# FTDIJtagConversion.net
KiCad netlist of a schematic drawn in Altium Designer
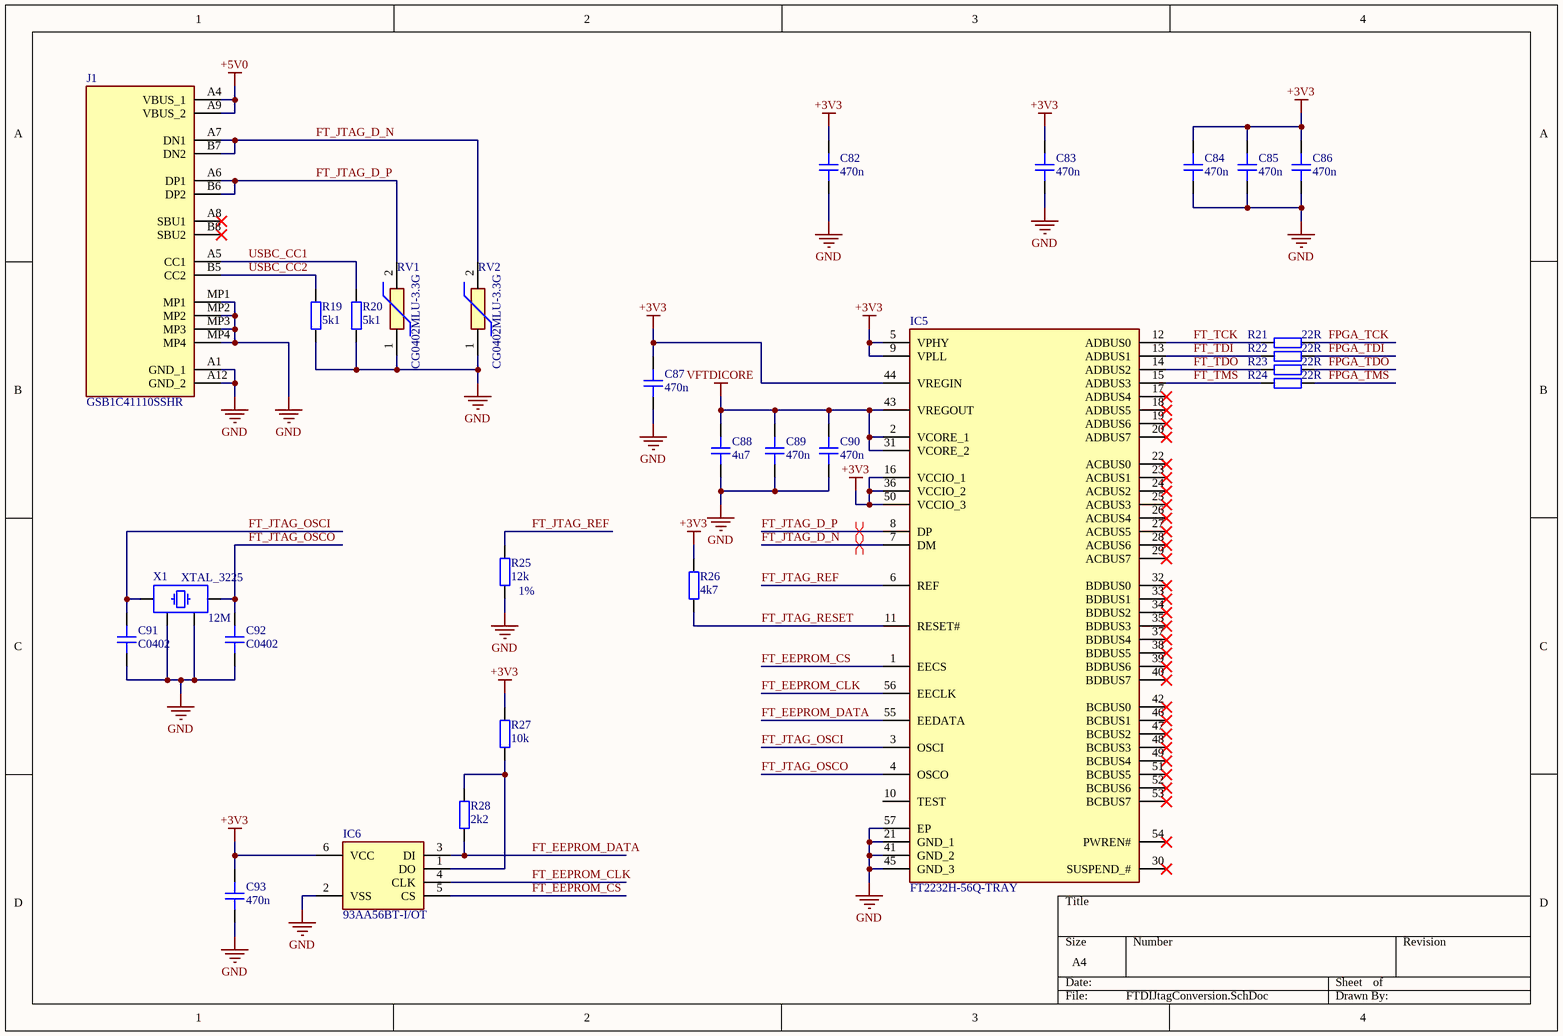
[diagram p0: FTDIJtagConversion.SchDoc]

(export (version "E")
  (design (tool "Eeschema 10.0.6"))
  (components
    (comp (ref "C82")
      (value "470n")
      (footprint "CAP_0201")
      (description "Capacitor SMD 0201")
      (libsource (lib "Schematic-Lib-PhilsLab") (part "CAP_0201"))
    )
    (comp (ref "C83")
      (value "470n")
      (footprint "CAP_0201")
      (description "Capacitor SMD 0201")
      (libsource (lib "Schematic-Lib-PhilsLab") (part "CAP_0201"))
    )
    (comp (ref "C84")
      (value "470n")
      (footprint "CAP_0201")
      (description "Capacitor SMD 0201")
      (libsource (lib "Schematic-Lib-PhilsLab") (part "CAP_0201"))
    )
    (comp (ref "C85")
      (value "470n")
      (footprint "CAP_0201")
      (description "Capacitor SMD 0201")
      (libsource (lib "Schematic-Lib-PhilsLab") (part "CAP_0201"))
    )
    (comp (ref "C86")
      (value "470n")
      (footprint "CAP_0201")
      (description "Capacitor SMD 0201")
      (libsource (lib "Schematic-Lib-PhilsLab") (part "CAP_0201"))
    )
    (comp (ref "C87")
      (value "470n")
      (footprint "CAP_0201")
      (description "Capacitor SMD 0201")
      (libsource (lib "Schematic-Lib-PhilsLab") (part "CAP_0201"))
    )
    (comp (ref "C88")
      (value "4u7")
      (footprint "CAP_0402")
      (description "Capacitor SMD 0402")
      (libsource (lib "Schematic-Lib-PhilsLab") (part "CAP_0402"))
    )
    (comp (ref "C89")
      (value "470n")
      (footprint "CAP_0201")
      (description "Capacitor SMD 0201")
      (libsource (lib "Schematic-Lib-PhilsLab") (part "CAP_0201"))
    )
    (comp (ref "C90")
      (value "470n")
      (footprint "CAP_0201")
      (description "Capacitor SMD 0201")
      (libsource (lib "Schematic-Lib-PhilsLab") (part "CAP_0201"))
    )
    (comp (ref "C91")
      (value "C0402")
      (footprint "CAP_0402")
      (description "Capacitor SMD 0402")
      (libsource (lib "Schematic-Lib-PhilsLab") (part "CAP_0402"))
    )
    (comp (ref "C92")
      (value "C0402")
      (footprint "CAP_0402")
      (description "Capacitor SMD 0402")
      (libsource (lib "Schematic-Lib-PhilsLab") (part "CAP_0402"))
    )
    (comp (ref "C93")
      (value "470n")
      (footprint "CAP_0201")
      (description "Capacitor SMD 0201")
      (libsource (lib "Schematic-Lib-PhilsLab") (part "CAP_0201"))
    )
    (comp (ref "IC5")
      (value "FT2232H-56Q-TRAY")
      (footprint "Footprint-Lib-PhilsLab:QFN50P800X800X100-57N-D")
      (description "Integrated Circuit")
      (fields (field (name "MOUSER PART NUMBER") "895-FT2232H-56Q-TRAY"))
      (libsource (lib "Schematic-Lib-PhilsLab") (part "FT2232H-56Q-TRAY"))
    )
    (comp (ref "IC6")
      (value "93AA56BT-I/OT")
      (footprint "Footprint-Lib-PhilsLab:SOT95P270X145-6N")
      (description "EEPROM")
      (fields (field (name "MOUSER PART NUMBER") "579-93AA56BT-I/OT"))
      (libsource (lib "Schematic-Lib-PhilsLab") (part "93AA56BT-I/OT"))
    )
    (comp (ref "J1")
      (value "GSB1C41110SSHR")
      (footprint "Footprint-Lib-PhilsLab:GSB1C41110SSHR")
      (description "Connector")
      (libsource (lib "Schematic-Lib-PhilsLab") (part "GSB1C41110SSHR"))
    )
    (comp (ref "R19")
      (value "5k1")
      (footprint "RES_0402")
      (description "Resistor SMD 0402")
      (libsource (lib "Schematic-Lib-PhilsLab") (part "RES_0402"))
    )
    (comp (ref "R20")
      (value "5k1")
      (footprint "RES_0402")
      (description "Resistor SMD 0402")
      (libsource (lib "Schematic-Lib-PhilsLab") (part "RES_0402"))
    )
    (comp (ref "R21")
      (value "22R")
      (footprint "RES_0201")
      (description "Resistor SMD 0201")
      (libsource (lib "Schematic-Lib-PhilsLab") (part "RES_0201"))
    )
    (comp (ref "R22")
      (value "22R")
      (footprint "RES_0201")
      (description "Resistor SMD 0201")
      (libsource (lib "Schematic-Lib-PhilsLab") (part "RES_0201"))
    )
    (comp (ref "R23")
      (value "22R")
      (footprint "RES_0201")
      (description "Resistor SMD 0201")
      (libsource (lib "Schematic-Lib-PhilsLab") (part "RES_0201"))
    )
    (comp (ref "R24")
      (value "22R")
      (footprint "RES_0201")
      (description "Resistor SMD 0201")
      (libsource (lib "Schematic-Lib-PhilsLab") (part "RES_0201"))
    )
    (comp (ref "R25")
      (value "12k")
      (footprint "RES_0402")
      (description "Resistor SMD 0402")
      (libsource (lib "Schematic-Lib-PhilsLab") (part "RES_0402"))
    )
    (comp (ref "R26")
      (value "4k7")
      (footprint "RES_0201")
      (description "Resistor SMD 0201")
      (libsource (lib "Schematic-Lib-PhilsLab") (part "RES_0201"))
    )
    (comp (ref "R27")
      (value "10k")
      (footprint "RES_0402")
      (description "Resistor SMD 0402")
      (libsource (lib "Schematic-Lib-PhilsLab") (part "RES_0402"))
    )
    (comp (ref "R28")
      (value "2k2")
      (footprint "RES_0402")
      (description "Resistor SMD 0402")
      (libsource (lib "Schematic-Lib-PhilsLab") (part "RES_0402"))
    )
    (comp (ref "RV1")
      (value "CG0402MLU-3.3G")
      (footprint "Footprint-Lib-PhilsLab:VARC1005X41N")
      (description "ESD Diode")
      (fields (field (name "MOUSER PART NUMBER") "652-CG0402MLU-3.3G"))
      (libsource (lib "Schematic-Lib-PhilsLab") (part "CG0402MLU-3.3G"))
    )
    (comp (ref "RV2")
      (value "CG0402MLU-3.3G")
      (footprint "Footprint-Lib-PhilsLab:VARC1005X41N")
      (description "ESD Diode")
      (fields (field (name "MOUSER PART NUMBER") "652-CG0402MLU-3.3G"))
      (libsource (lib "Schematic-Lib-PhilsLab") (part "CG0402MLU-3.3G"))
    )
    (comp (ref "X1")
      (value "XTAL_3225")
      (footprint "XTAL_3225")
      (description "Crystal SMD 3225")
      (libsource (lib "Schematic-Lib-PhilsLab") (part "XTAL_3225"))
    )
  )
  (nets
    (net (code "1") (name "+3V3") (class "Default")
      (node (ref "C82") (pin "2") (pinfunction "2_2") (pintype "passive"))
      (node (ref "C83") (pin "2") (pinfunction "2_2") (pintype "passive"))
      (node (ref "C84") (pin "2") (pinfunction "2_2") (pintype "passive"))
      (node (ref "C85") (pin "2") (pinfunction "2_2") (pintype "passive"))
      (node (ref "C86") (pin "2") (pinfunction "2_2") (pintype "passive"))
      (node (ref "C87") (pin "2") (pinfunction "2_2") (pintype "passive"))
      (node (ref "C93") (pin "2") (pinfunction "2_2") (pintype "passive"))
      (node (ref "IC5") (pin "16") (pinfunction "VCCIO_1_16") (pintype "passive"))
      (node (ref "IC5") (pin "36") (pinfunction "VCCIO_2_36") (pintype "passive"))
      (node (ref "IC5") (pin "44") (pinfunction "VREGIN_44") (pintype "passive"))
      (node (ref "IC5") (pin "5") (pinfunction "VPHY_5") (pintype "passive"))
      (node (ref "IC5") (pin "50") (pinfunction "VCCIO_3_50") (pintype "passive"))
      (node (ref "IC5") (pin "9") (pinfunction "VPLL_9") (pintype "passive"))
      (node (ref "IC6") (pin "6") (pinfunction "VCC_6") (pintype "passive"))
      (node (ref "R26") (pin "2") (pinfunction "2_2") (pintype "passive"))
      (node (ref "R27") (pin "2") (pinfunction "2_2") (pintype "passive"))
    )
    (net (code "2") (name "+5V0") (class "Default")
      (node (ref "J1") (pin "A4") (pinfunction "VBUS_1_A4") (pintype "passive"))
      (node (ref "J1") (pin "A9") (pinfunction "VBUS_2_A9") (pintype "passive"))
    )
    (net (code "3") (name "/FPGA_TCK") (class "Default")
      (node (ref "R21") (pin "1") (pinfunction "1_1") (pintype "passive"))
    )
    (net (code "4") (name "/FPGA_TDI") (class "Default")
      (node (ref "R22") (pin "1") (pinfunction "1_1") (pintype "passive"))
    )
    (net (code "5") (name "/FPGA_TDO") (class "Default")
      (node (ref "R23") (pin "1") (pinfunction "1_1") (pintype "passive"))
    )
    (net (code "6") (name "/FPGA_TMS") (class "Default")
      (node (ref "R24") (pin "1") (pinfunction "1_1") (pintype "passive"))
    )
    (net (code "7") (name "/FT_EEPROM_CLK") (class "Default")
      (node (ref "IC5") (pin "56") (pinfunction "EECLK_56") (pintype "passive"))
      (node (ref "IC6") (pin "4") (pinfunction "CLK_4") (pintype "passive"))
    )
    (net (code "8") (name "/FT_EEPROM_CS") (class "Default")
      (node (ref "IC5") (pin "1") (pinfunction "EECS_1") (pintype "passive"))
      (node (ref "IC6") (pin "5") (pinfunction "CS_5") (pintype "passive"))
    )
    (net (code "9") (name "/FT_EEPROM_DATA") (class "Default")
      (node (ref "IC5") (pin "55") (pinfunction "EEDATA_55") (pintype "passive"))
      (node (ref "IC6") (pin "3") (pinfunction "DI_3") (pintype "passive"))
      (node (ref "R28") (pin "1") (pinfunction "1_1") (pintype "passive"))
    )
    (net (code "10") (name "/FT_JTAG_D_N") (class "Default")
      (node (ref "IC5") (pin "7") (pinfunction "DM_7") (pintype "passive"))
      (node (ref "J1") (pin "A7") (pinfunction "DN1_A7") (pintype "passive"))
      (node (ref "J1") (pin "B7") (pinfunction "DN2_B7") (pintype "passive"))
      (node (ref "RV2") (pin "2") (pinfunction "2_2") (pintype "passive"))
    )
    (net (code "11") (name "/FT_JTAG_D_P") (class "Default")
      (node (ref "IC5") (pin "8") (pinfunction "DP_8") (pintype "passive"))
      (node (ref "J1") (pin "A6") (pinfunction "DP1_A6") (pintype "passive"))
      (node (ref "J1") (pin "B6") (pinfunction "DP2_B6") (pintype "passive"))
      (node (ref "RV1") (pin "2") (pinfunction "2_2") (pintype "passive"))
    )
    (net (code "12") (name "/FT_JTAG_OSCI") (class "Default")
      (node (ref "C91") (pin "2") (pinfunction "2_2") (pintype "passive"))
      (node (ref "IC5") (pin "3") (pinfunction "OSCI_3") (pintype "passive"))
      (node (ref "X1") (pin "1") (pinfunction "1_1") (pintype "passive"))
    )
    (net (code "13") (name "/FT_JTAG_OSCO") (class "Default")
      (node (ref "C92") (pin "2") (pinfunction "2_2") (pintype "passive"))
      (node (ref "IC5") (pin "4") (pinfunction "OSCO_4") (pintype "passive"))
      (node (ref "X1") (pin "3") (pinfunction "3_3") (pintype "passive"))
    )
    (net (code "14") (name "/FT_JTAG_REF") (class "Default")
      (node (ref "IC5") (pin "6") (pinfunction "REF_6") (pintype "passive"))
      (node (ref "R25") (pin "2") (pinfunction "2_2") (pintype "passive"))
    )
    (net (code "15") (name "/FT_JTAG_RESET") (class "Default")
      (node (ref "IC5") (pin "11") (pinfunction "RESET#_11") (pintype "passive"))
      (node (ref "R26") (pin "1") (pinfunction "1_1") (pintype "passive"))
    )
    (net (code "16") (name "/FT_TCK") (class "Default")
      (node (ref "IC5") (pin "12") (pinfunction "ADBUS0_12") (pintype "passive"))
      (node (ref "R21") (pin "2") (pinfunction "2_2") (pintype "passive"))
    )
    (net (code "17") (name "/FT_TDI") (class "Default")
      (node (ref "IC5") (pin "13") (pinfunction "ADBUS1_13") (pintype "passive"))
      (node (ref "R22") (pin "2") (pinfunction "2_2") (pintype "passive"))
    )
    (net (code "18") (name "/FT_TDO") (class "Default")
      (node (ref "IC5") (pin "14") (pinfunction "ADBUS2_14") (pintype "passive"))
      (node (ref "R23") (pin "2") (pinfunction "2_2") (pintype "passive"))
    )
    (net (code "19") (name "/FT_TMS") (class "Default")
      (node (ref "IC5") (pin "15") (pinfunction "ADBUS3_15") (pintype "passive"))
      (node (ref "R24") (pin "2") (pinfunction "2_2") (pintype "passive"))
    )
    (net (code "20") (name "/USBC_CC1") (class "Default")
      (node (ref "J1") (pin "A5") (pinfunction "CC1_A5") (pintype "passive"))
      (node (ref "R20") (pin "2") (pinfunction "2_2") (pintype "passive"))
    )
    (net (code "21") (name "/USBC_CC2") (class "Default")
      (node (ref "J1") (pin "B5") (pinfunction "CC2_B5") (pintype "passive"))
      (node (ref "R19") (pin "2") (pinfunction "2_2") (pintype "passive"))
    )
    (net (code "22") (name "GND") (class "Default")
      (node (ref "C82") (pin "1") (pinfunction "1_1") (pintype "passive"))
      (node (ref "C83") (pin "1") (pinfunction "1_1") (pintype "passive"))
      (node (ref "C84") (pin "1") (pinfunction "1_1") (pintype "passive"))
      (node (ref "C85") (pin "1") (pinfunction "1_1") (pintype "passive"))
      (node (ref "C86") (pin "1") (pinfunction "1_1") (pintype "passive"))
      (node (ref "C87") (pin "1") (pinfunction "1_1") (pintype "passive"))
      (node (ref "C88") (pin "1") (pinfunction "1_1") (pintype "passive"))
      (node (ref "C89") (pin "1") (pinfunction "1_1") (pintype "passive"))
      (node (ref "C90") (pin "1") (pinfunction "1_1") (pintype "passive"))
      (node (ref "C91") (pin "1") (pinfunction "1_1") (pintype "passive"))
      (node (ref "C92") (pin "1") (pinfunction "1_1") (pintype "passive"))
      (node (ref "C93") (pin "1") (pinfunction "1_1") (pintype "passive"))
      (node (ref "IC5") (pin "21") (pinfunction "GND_1_21") (pintype "passive"))
      (node (ref "IC5") (pin "41") (pinfunction "GND_2_41") (pintype "passive"))
      (node (ref "IC5") (pin "45") (pinfunction "GND_3_45") (pintype "passive"))
      (node (ref "IC5") (pin "57") (pinfunction "EP_57") (pintype "passive"))
      (node (ref "IC6") (pin "2") (pinfunction "VSS_2") (pintype "passive"))
      (node (ref "J1") (pin "A1") (pinfunction "GND_1_A1") (pintype "passive"))
      (node (ref "J1") (pin "A12") (pinfunction "GND_2_A12") (pintype "passive"))
      (node (ref "J1") (pin "MP1") (pinfunction "MP1_MP1") (pintype "passive"))
      (node (ref "J1") (pin "MP2") (pinfunction "MP2_MP2") (pintype "passive"))
      (node (ref "J1") (pin "MP3") (pinfunction "MP3_MP3") (pintype "passive"))
      (node (ref "J1") (pin "MP4") (pinfunction "MP4_MP4") (pintype "passive"))
      (node (ref "R19") (pin "1") (pinfunction "1_1") (pintype "passive"))
      (node (ref "R20") (pin "1") (pinfunction "1_1") (pintype "passive"))
      (node (ref "R25") (pin "1") (pinfunction "1_1") (pintype "passive"))
      (node (ref "RV1") (pin "1") (pinfunction "1_1") (pintype "passive"))
      (node (ref "RV2") (pin "1") (pinfunction "1_1") (pintype "passive"))
      (node (ref "X1") (pin "2") (pinfunction "2_2") (pintype "passive"))
      (node (ref "X1") (pin "4") (pinfunction "4_4") (pintype "passive"))
    )
    (net (code "23") (name "Net-(IC6-DO)") (class "Default")
      (node (ref "IC6") (pin "1") (pinfunction "DO_1") (pintype "passive"))
      (node (ref "R27") (pin "1") (pinfunction "1_1") (pintype "passive"))
      (node (ref "R28") (pin "2") (pinfunction "2_2") (pintype "passive"))
    )
    (net (code "24") (name "VFTDICORE") (class "Default")
      (node (ref "C88") (pin "2") (pinfunction "2_2") (pintype "passive"))
      (node (ref "C89") (pin "2") (pinfunction "2_2") (pintype "passive"))
      (node (ref "C90") (pin "2") (pinfunction "2_2") (pintype "passive"))
      (node (ref "IC5") (pin "2") (pinfunction "VCORE_1_2") (pintype "passive"))
      (node (ref "IC5") (pin "31") (pinfunction "VCORE_2_31") (pintype "passive"))
      (node (ref "IC5") (pin "43") (pinfunction "VREGOUT_43") (pintype "passive"))
    )
    (net (code "25") (name "unconnected-(IC5-ACBUS0-Pad22)") (class "Default")
      (node (ref "IC5") (pin "22") (pinfunction "ACBUS0_22") (pintype "passive+no_connect"))
    )
    (net (code "26") (name "unconnected-(IC5-ACBUS1-Pad23)") (class "Default")
      (node (ref "IC5") (pin "23") (pinfunction "ACBUS1_23") (pintype "passive+no_connect"))
    )
    (net (code "27") (name "unconnected-(IC5-ACBUS2-Pad24)") (class "Default")
      (node (ref "IC5") (pin "24") (pinfunction "ACBUS2_24") (pintype "passive+no_connect"))
    )
    (net (code "28") (name "unconnected-(IC5-ACBUS3-Pad25)") (class "Default")
      (node (ref "IC5") (pin "25") (pinfunction "ACBUS3_25") (pintype "passive+no_connect"))
    )
    (net (code "29") (name "unconnected-(IC5-ACBUS4-Pad26)") (class "Default")
      (node (ref "IC5") (pin "26") (pinfunction "ACBUS4_26") (pintype "passive+no_connect"))
    )
    (net (code "30") (name "unconnected-(IC5-ACBUS5-Pad27)") (class "Default")
      (node (ref "IC5") (pin "27") (pinfunction "ACBUS5_27") (pintype "passive+no_connect"))
    )
    (net (code "31") (name "unconnected-(IC5-ACBUS6-Pad28)") (class "Default")
      (node (ref "IC5") (pin "28") (pinfunction "ACBUS6_28") (pintype "passive+no_connect"))
    )
    (net (code "32") (name "unconnected-(IC5-ACBUS7-Pad29)") (class "Default")
      (node (ref "IC5") (pin "29") (pinfunction "ACBUS7_29") (pintype "passive+no_connect"))
    )
    (net (code "33") (name "unconnected-(IC5-ADBUS4-Pad17)") (class "Default")
      (node (ref "IC5") (pin "17") (pinfunction "ADBUS4_17") (pintype "passive+no_connect"))
    )
    (net (code "34") (name "unconnected-(IC5-ADBUS5-Pad18)") (class "Default")
      (node (ref "IC5") (pin "18") (pinfunction "ADBUS5_18") (pintype "passive+no_connect"))
    )
    (net (code "35") (name "unconnected-(IC5-ADBUS6-Pad19)") (class "Default")
      (node (ref "IC5") (pin "19") (pinfunction "ADBUS6_19") (pintype "passive+no_connect"))
    )
    (net (code "36") (name "unconnected-(IC5-ADBUS7-Pad20)") (class "Default")
      (node (ref "IC5") (pin "20") (pinfunction "ADBUS7_20") (pintype "passive+no_connect"))
    )
    (net (code "37") (name "unconnected-(IC5-BCBUS0-Pad42)") (class "Default")
      (node (ref "IC5") (pin "42") (pinfunction "BCBUS0_42") (pintype "passive+no_connect"))
    )
    (net (code "38") (name "unconnected-(IC5-BCBUS1-Pad46)") (class "Default")
      (node (ref "IC5") (pin "46") (pinfunction "BCBUS1_46") (pintype "passive+no_connect"))
    )
    (net (code "39") (name "unconnected-(IC5-BCBUS2-Pad47)") (class "Default")
      (node (ref "IC5") (pin "47") (pinfunction "BCBUS2_47") (pintype "passive+no_connect"))
    )
    (net (code "40") (name "unconnected-(IC5-BCBUS3-Pad48)") (class "Default")
      (node (ref "IC5") (pin "48") (pinfunction "BCBUS3_48") (pintype "passive+no_connect"))
    )
    (net (code "41") (name "unconnected-(IC5-BCBUS4-Pad49)") (class "Default")
      (node (ref "IC5") (pin "49") (pinfunction "BCBUS4_49") (pintype "passive+no_connect"))
    )
    (net (code "42") (name "unconnected-(IC5-BCBUS5-Pad51)") (class "Default")
      (node (ref "IC5") (pin "51") (pinfunction "BCBUS5_51") (pintype "passive+no_connect"))
    )
    (net (code "43") (name "unconnected-(IC5-BCBUS6-Pad52)") (class "Default")
      (node (ref "IC5") (pin "52") (pinfunction "BCBUS6_52") (pintype "passive+no_connect"))
    )
    (net (code "44") (name "unconnected-(IC5-BCBUS7-Pad53)") (class "Default")
      (node (ref "IC5") (pin "53") (pinfunction "BCBUS7_53") (pintype "passive+no_connect"))
    )
    (net (code "45") (name "unconnected-(IC5-BDBUS0-Pad32)") (class "Default")
      (node (ref "IC5") (pin "32") (pinfunction "BDBUS0_32") (pintype "passive+no_connect"))
    )
    (net (code "46") (name "unconnected-(IC5-BDBUS1-Pad33)") (class "Default")
      (node (ref "IC5") (pin "33") (pinfunction "BDBUS1_33") (pintype "passive+no_connect"))
    )
    (net (code "47") (name "unconnected-(IC5-BDBUS2-Pad34)") (class "Default")
      (node (ref "IC5") (pin "34") (pinfunction "BDBUS2_34") (pintype "passive+no_connect"))
    )
    (net (code "48") (name "unconnected-(IC5-BDBUS3-Pad35)") (class "Default")
      (node (ref "IC5") (pin "35") (pinfunction "BDBUS3_35") (pintype "passive+no_connect"))
    )
    (net (code "49") (name "unconnected-(IC5-BDBUS4-Pad37)") (class "Default")
      (node (ref "IC5") (pin "37") (pinfunction "BDBUS4_37") (pintype "passive+no_connect"))
    )
    (net (code "50") (name "unconnected-(IC5-BDBUS5-Pad38)") (class "Default")
      (node (ref "IC5") (pin "38") (pinfunction "BDBUS5_38") (pintype "passive+no_connect"))
    )
    (net (code "51") (name "unconnected-(IC5-BDBUS6-Pad39)") (class "Default")
      (node (ref "IC5") (pin "39") (pinfunction "BDBUS6_39") (pintype "passive+no_connect"))
    )
    (net (code "52") (name "unconnected-(IC5-BDBUS7-Pad40)") (class "Default")
      (node (ref "IC5") (pin "40") (pinfunction "BDBUS7_40") (pintype "passive+no_connect"))
    )
    (net (code "53") (name "unconnected-(IC5-PWREN#-Pad54)") (class "Default")
      (node (ref "IC5") (pin "54") (pinfunction "PWREN#_54") (pintype "passive+no_connect"))
    )
    (net (code "54") (name "unconnected-(IC5-SUSPEND_#-Pad30)") (class "Default")
      (node (ref "IC5") (pin "30") (pinfunction "SUSPEND_#_30") (pintype "passive+no_connect"))
    )
    (net (code "55") (name "unconnected-(IC5-TEST-Pad10)") (class "Default")
      (node (ref "IC5") (pin "10") (pinfunction "TEST_10") (pintype "passive"))
    )
    (net (code "56") (name "unconnected-(J1-SBU1-PadA8)") (class "Default")
      (node (ref "J1") (pin "A8") (pinfunction "SBU1_A8") (pintype "passive+no_connect"))
    )
    (net (code "57") (name "unconnected-(J1-SBU2-PadB8)") (class "Default")
      (node (ref "J1") (pin "B8") (pinfunction "SBU2_B8") (pintype "passive+no_connect"))
    )
  )
)
